# Analog_Attenuator.net
KiCad netlist of a schematic drawn in Altium Designer
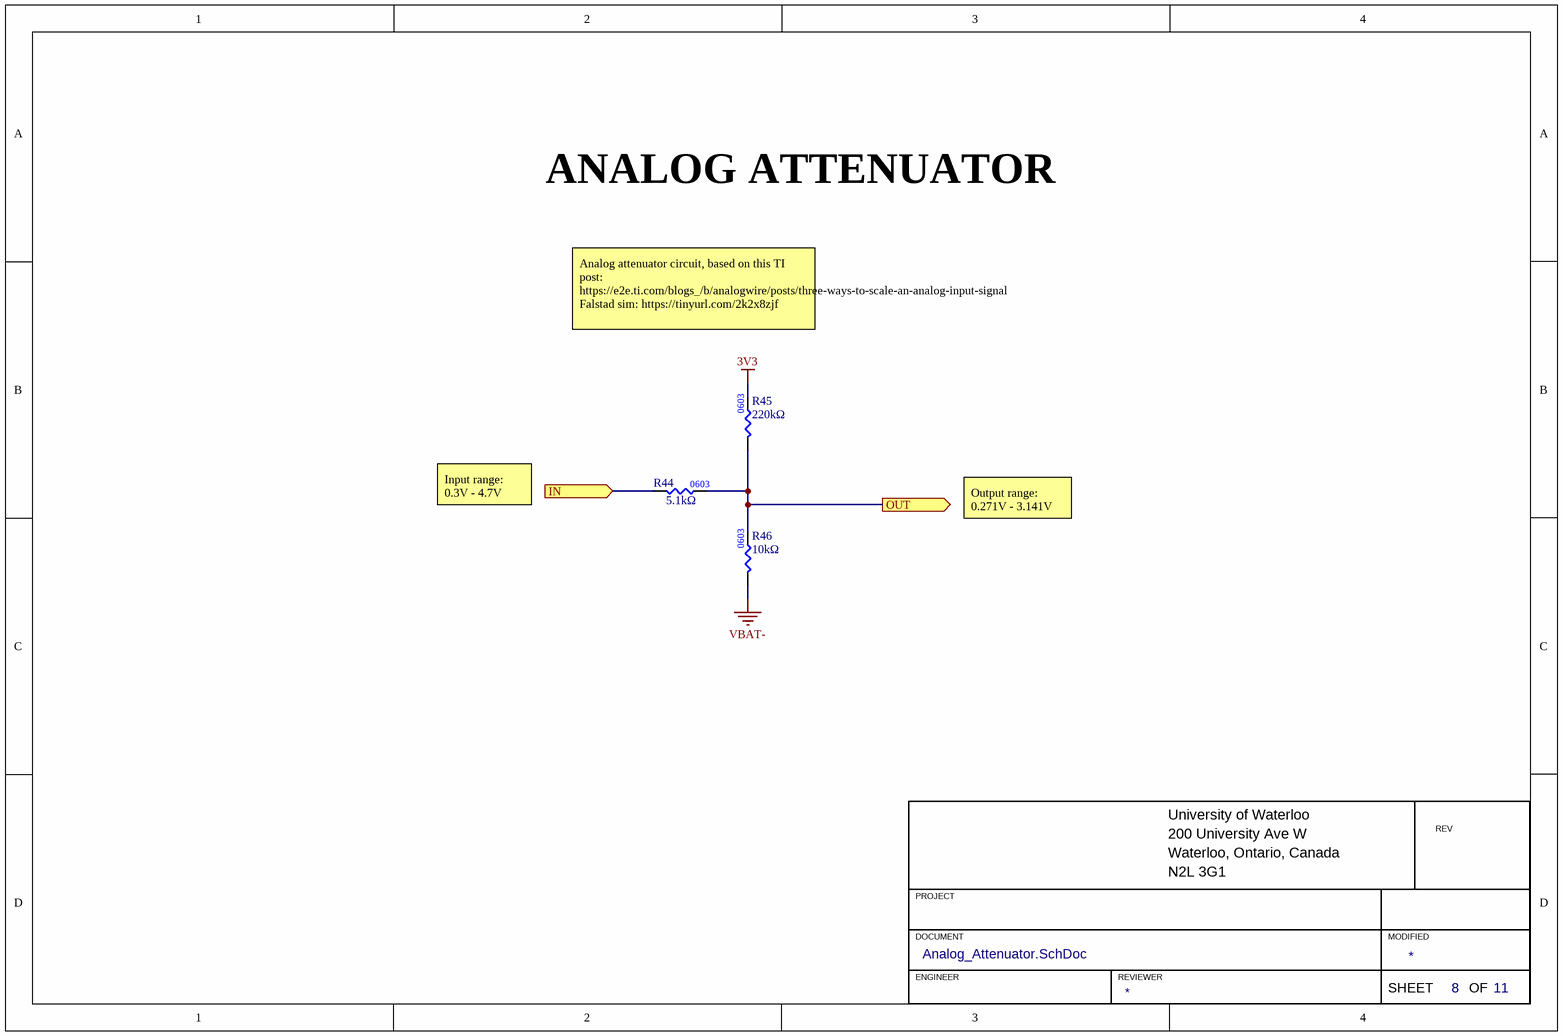
[diagram p0: Analog_Attenuator.SchDoc]

(export (version "E")
  (design (tool "Eeschema 10.0.6"))
  (components
    (comp (ref "R44")
      (value "5.1kΩ")
      (footprint "RES0603")
      (description "RES 5.1K OHM 1% 1/10W 0603")
      (fields (field (name "Comment") "RES_5.1kΩ_0603_1%"))
      (libsource (lib "Personal_Schematic_Library_2022") (part "RES_5.1kΩ_0603_1%"))
    )
    (comp (ref "R45")
      (value "220kΩ")
      (footprint "RES0603")
      (description "RES 220K OHM 1% 1/10W 0603")
      (fields (field (name "TOLERANCE") "1%") (field (name "Comment") "RES_220kΩ_0603_1%"))
      (libsource (lib "Personal_Schematic_Library_2022") (part "RES_220kΩ_0603_1%"))
    )
    (comp (ref "R46")
      (value "10kΩ")
      (footprint "RES0603")
      (description "RES 10K OHM 1% 1/8W 0603")
      (fields (field (name "Comment") "RES_10kΩ_0603_1%"))
      (libsource (lib "Personal_Schematic_Library_2022") (part "RES_10kΩ_0603_1%"))
    )
  )
  (nets
    (net (code "1") (name "/IN") (class "Default")
      (node (ref "R44") (pin "1") (pinfunction "1_1") (pintype "passive"))
    )
    (net (code "2") (name "/OUT") (class "Default")
      (node (ref "R44") (pin "2") (pinfunction "2_2") (pintype "passive"))
      (node (ref "R45") (pin "1") (pinfunction "1_1") (pintype "passive"))
      (node (ref "R46") (pin "2") (pinfunction "2_2") (pintype "passive"))
    )
    (net (code "3") (name "3V3") (class "Default")
      (node (ref "R45") (pin "2") (pinfunction "2_2") (pintype "passive"))
    )
    (net (code "4") (name "VBAT-") (class "Default")
      (node (ref "R46") (pin "1") (pinfunction "1_1") (pintype "passive"))
    )
  )
)
